# source_eagle.net
KiCad netlist of a schematic drawn in EAGLE
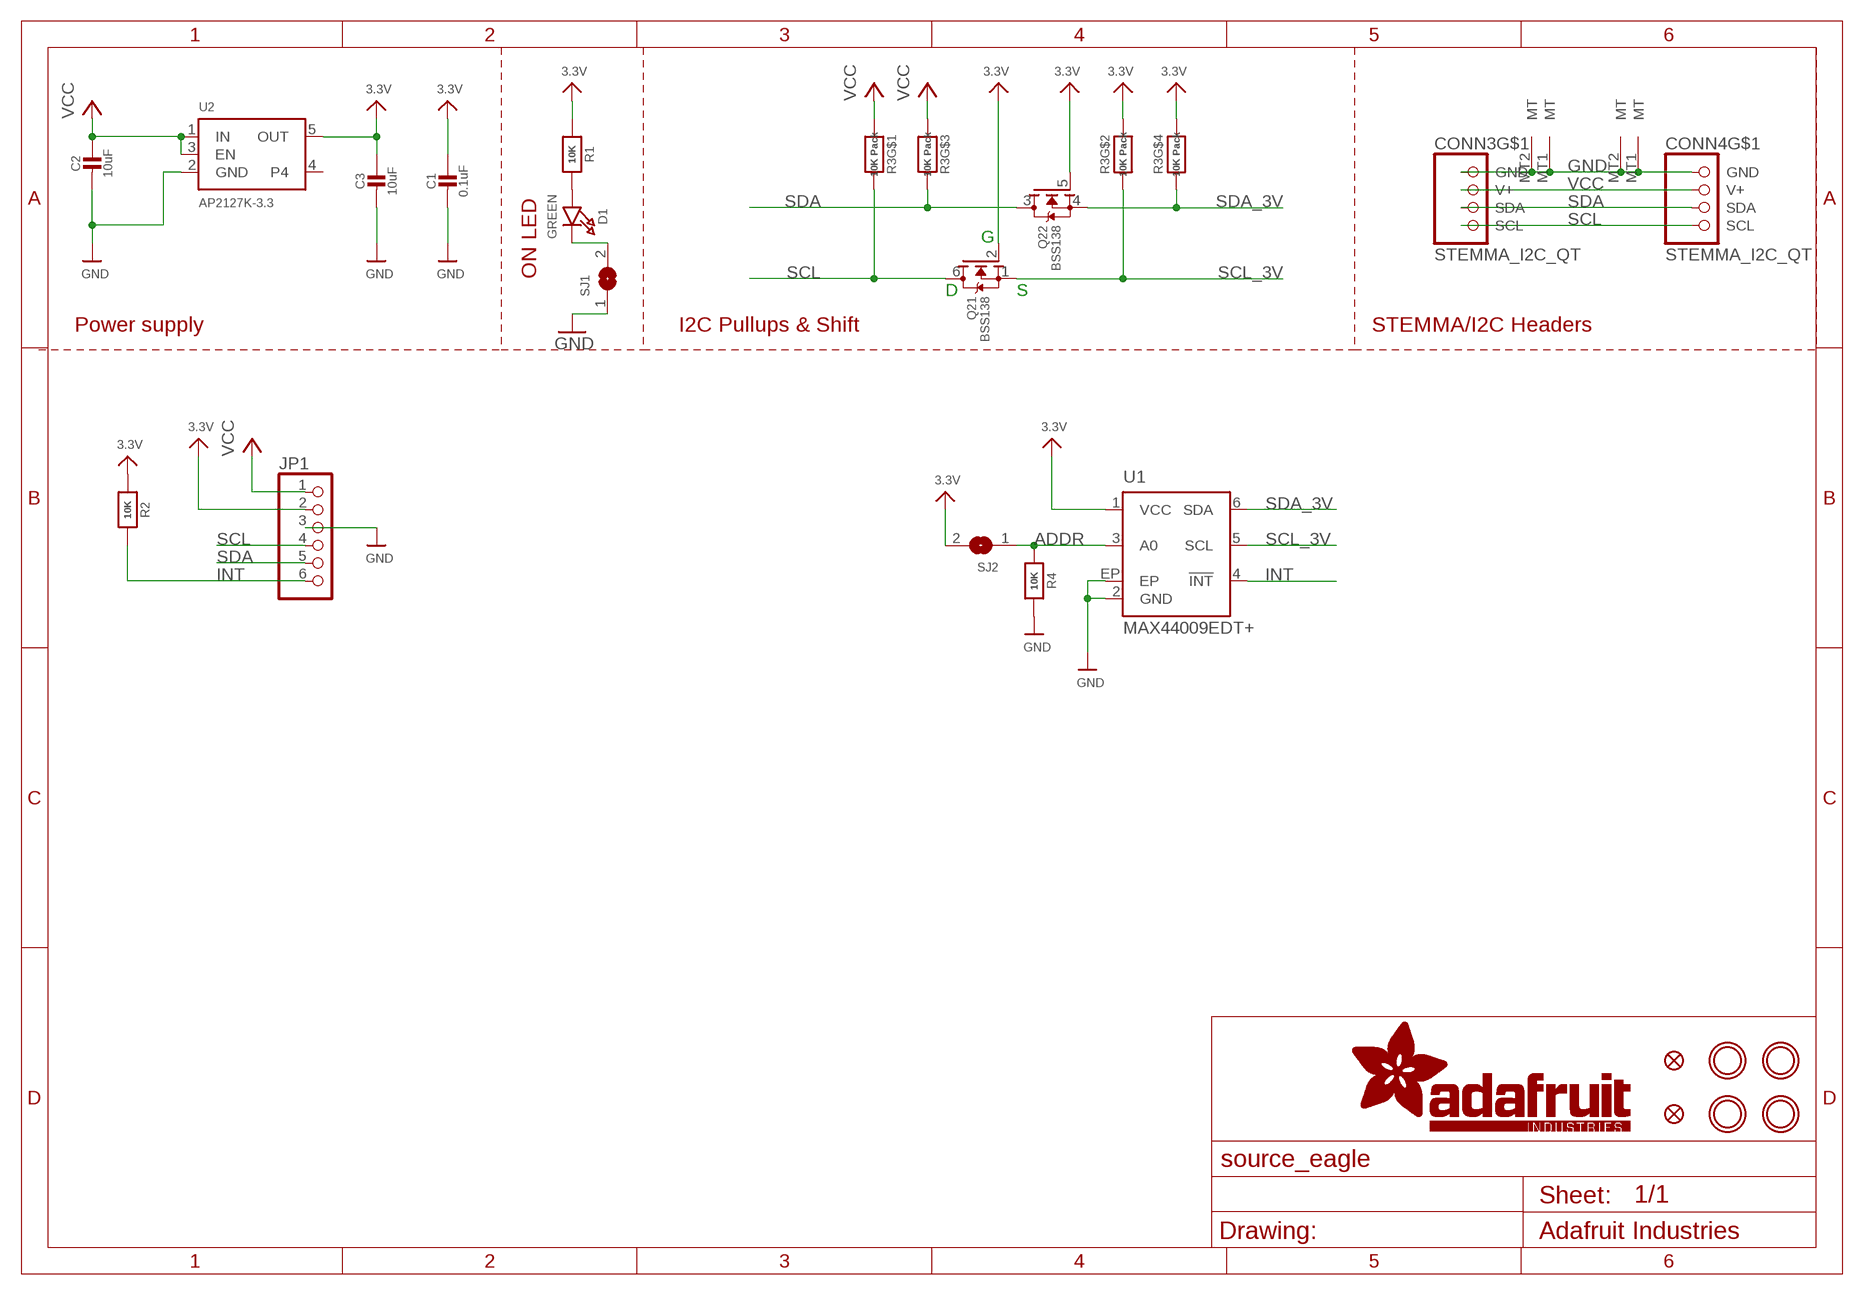
[diagram p0: schematic, sheet 1]

(export (version "E")
  (design (tool "Eeschema 10.0.6"))
  (components
    (comp (ref "C1")
      (value "0.1uF")
      (footprint "eagle-import:0603-NO")
      (libsource (lib "eagle-import") (part "CAP_CERAMIC0603_NO"))
    )
    (comp (ref "C2")
      (value "10uF")
      (footprint "eagle-import:0805-NO")
      (libsource (lib "eagle-import") (part "CAP_CERAMIC0805-NOOUTLINE"))
    )
    (comp (ref "C3")
      (value "10uF")
      (footprint "eagle-import:0805-NO")
      (libsource (lib "eagle-import") (part "CAP_CERAMIC0805-NOOUTLINE"))
    )
    (comp (ref "CONN3")
      (value "STEMMA_I2C_QT")
      (footprint "eagle-import:JST_SH4")
      (libsource (lib "eagle-import") (part "STEMMA_I2C_QT"))
    )
    (comp (ref "CONN4")
      (value "STEMMA_I2C_QT")
      (footprint "eagle-import:JST_SH4")
      (libsource (lib "eagle-import") (part "STEMMA_I2C_QT"))
    )
    (comp (ref "D1")
      (value "GREEN")
      (footprint "eagle-import:CHIPLED_0603_NOOUTLINE")
      (libsource (lib "eagle-import") (part "LED0603_NOOUTLINE"))
    )
    (comp (ref "FID3")
      (value "FIDUCIAL_0.5MM")
      (footprint "eagle-import:FIDUCIAL_0.5MM")
      (libsource (lib "eagle-import") (part "FIDUCIAL_0.5MM"))
    )
    (comp (ref "FID4")
      (value "FIDUCIAL_0.5MM")
      (footprint "eagle-import:FIDUCIAL_0.5MM")
      (libsource (lib "eagle-import") (part "FIDUCIAL_0.5MM"))
    )
    (comp (ref "JP1")
      (value "HEADER-1X670MIL")
      (footprint "eagle-import:1X06_ROUND_70")
      (libsource (lib "eagle-import") (part "HEADER-1X670MIL"))
    )
    (comp (ref "Q2")
      (value "BSS138")
      (footprint "eagle-import:SOT363")
      (libsource (lib "eagle-import") (part "MOSFET-N_DUAL"))
    )
    (comp (ref "R1")
      (value "10K")
      (footprint "eagle-import:0603-NO")
      (libsource (lib "eagle-import") (part "RESISTOR_0603_NOOUT"))
    )
    (comp (ref "R2")
      (value "10K")
      (footprint "eagle-import:0603-NO")
      (libsource (lib "eagle-import") (part "RESISTOR_0603_NOOUT"))
    )
    (comp (ref "R3")
      (value "10K Pack")
      (footprint "eagle-import:RESPACK_4X0603")
      (libsource (lib "eagle-import") (part "RESISTOR_4PACK"))
    )
    (comp (ref "R4")
      (value "10K")
      (footprint "eagle-import:0603-NO")
      (libsource (lib "eagle-import") (part "RESISTOR_0603_NOOUT"))
    )
    (comp (ref "SJ1")
      (value "SOLDERJUMPERCLOSED")
      (footprint "eagle-import:SOLDERJUMPER_CLOSEDWIRE")
      (libsource (lib "eagle-import") (part "SOLDERJUMPERCLOSED"))
    )
    (comp (ref "SJ2")
      (value "SOLDERJUMPER")
      (footprint "eagle-import:SOLDERJUMPER_ARROW_NOPASTE")
      (libsource (lib "eagle-import") (part "SOLDERJUMPER"))
    )
    (comp (ref "U$1")
      (value "MOUNTINGHOLE2.5")
      (footprint "eagle-import:MOUNTINGHOLE_2.5_PLATED")
      (libsource (lib "eagle-import") (part "MOUNTINGHOLE2.5"))
    )
    (comp (ref "U$17")
      (value "MOUNTINGHOLE2.5")
      (footprint "eagle-import:MOUNTINGHOLE_2.5_PLATED")
      (libsource (lib "eagle-import") (part "MOUNTINGHOLE2.5"))
    )
    (comp (ref "U$19")
      (value "MOUNTINGHOLE2.5")
      (footprint "eagle-import:MOUNTINGHOLE_2.5_PLATED")
      (libsource (lib "eagle-import") (part "MOUNTINGHOLE2.5"))
    )
    (comp (ref "U$21")
      (value "MOUNTINGHOLE2.5")
      (footprint "eagle-import:MOUNTINGHOLE_2.5_PLATED")
      (libsource (lib "eagle-import") (part "MOUNTINGHOLE2.5"))
    )
    (comp (ref "U1")
      (value "MAX44009EDT+")
      (footprint "eagle-import:UTDFN-OPTO-6")
      (libsource (lib "eagle-import") (part "MAX44009EDT+"))
    )
    (comp (ref "U2")
      (value "AP2127K-3.3")
      (footprint "eagle-import:SOT23-5")
      (libsource (lib "eagle-import") (part "VREG_SOT23-5"))
    )
  )
  (nets
    (net (code "1") (name "/ADDR") (class "Default")
      (node (ref "R4") (pin "1") (pinfunction "1_1") (pintype "passive"))
      (node (ref "SJ2") (pin "1") (pinfunction "1_1") (pintype "passive"))
      (node (ref "U1") (pin "3") (pinfunction "A0_3") (pintype "input"))
    )
    (net (code "2") (name "/INT") (class "Default")
      (node (ref "JP1") (pin "6") (pinfunction "6_6") (pintype "passive"))
      (node (ref "R2") (pin "2") (pinfunction "2_2") (pintype "passive"))
      (node (ref "U1") (pin "4") (pinfunction "~{INT}_4") (pintype "open_collector"))
    )
    (net (code "3") (name "/SCL") (class "Default")
      (node (ref "CONN3") (pin "4") (pinfunction "SCL_4") (pintype "passive"))
      (node (ref "CONN4") (pin "4") (pinfunction "SCL_4") (pintype "passive"))
      (node (ref "JP1") (pin "4") (pinfunction "4_4") (pintype "passive"))
      (node (ref "Q2") (pin "6") (pinfunction "D_6") (pintype "bidirectional"))
      (node (ref "R3") (pin "8") (pinfunction "2_8") (pintype "passive"))
    )
    (net (code "4") (name "/SCL_3V") (class "Default")
      (node (ref "Q2") (pin "1") (pinfunction "S_1") (pintype "bidirectional"))
      (node (ref "R3") (pin "7") (pinfunction "2_7") (pintype "passive"))
      (node (ref "U1") (pin "5") (pinfunction "SCL_5") (pintype "input"))
    )
    (net (code "5") (name "/SDA") (class "Default")
      (node (ref "CONN3") (pin "3") (pinfunction "SDA_3") (pintype "passive"))
      (node (ref "CONN4") (pin "3") (pinfunction "SDA_3") (pintype "passive"))
      (node (ref "JP1") (pin "5") (pinfunction "5_5") (pintype "passive"))
      (node (ref "Q2") (pin "3") (pinfunction "D_3") (pintype "bidirectional"))
      (node (ref "R3") (pin "6") (pinfunction "2_6") (pintype "passive"))
    )
    (net (code "6") (name "/SDA_3V") (class "Default")
      (node (ref "Q2") (pin "4") (pinfunction "S_4") (pintype "bidirectional"))
      (node (ref "R3") (pin "5") (pinfunction "2_5") (pintype "passive"))
      (node (ref "U1") (pin "6") (pinfunction "SDA_6") (pintype "bidirectional"))
    )
    (net (code "7") (name "3.3V") (class "Default")
      (node (ref "C1") (pin "1") (pinfunction "1_1") (pintype "passive"))
      (node (ref "C3") (pin "1") (pinfunction "1_1") (pintype "passive"))
      (node (ref "JP1") (pin "2") (pinfunction "2_2") (pintype "passive"))
      (node (ref "Q2") (pin "2") (pinfunction "G_2") (pintype "bidirectional"))
      (node (ref "Q2") (pin "5") (pinfunction "G_5") (pintype "bidirectional"))
      (node (ref "R1") (pin "1") (pinfunction "1_1") (pintype "passive"))
      (node (ref "R2") (pin "1") (pinfunction "1_1") (pintype "passive"))
      (node (ref "R3") (pin "2") (pinfunction "1_2") (pintype "passive"))
      (node (ref "R3") (pin "4") (pinfunction "1_4") (pintype "passive"))
      (node (ref "SJ2") (pin "2") (pinfunction "2_2") (pintype "passive"))
      (node (ref "U1") (pin "1") (pinfunction "VCC_1") (pintype "power_in"))
      (node (ref "U2") (pin "5") (pinfunction "OUT_5") (pintype "power_in"))
    )
    (net (code "8") (name "GND") (class "Default")
      (node (ref "C1") (pin "2") (pinfunction "2_2") (pintype "passive"))
      (node (ref "C2") (pin "2") (pinfunction "2_2") (pintype "passive"))
      (node (ref "C3") (pin "2") (pinfunction "2_2") (pintype "passive"))
      (node (ref "CONN3") (pin "1") (pinfunction "GND_1") (pintype "passive"))
      (node (ref "CONN3") (pin "MT1") (pinfunction "MT_MT1") (pintype "bidirectional"))
      (node (ref "CONN3") (pin "MT2") (pinfunction "MT_MT2") (pintype "bidirectional"))
      (node (ref "CONN4") (pin "1") (pinfunction "GND_1") (pintype "passive"))
      (node (ref "CONN4") (pin "MT1") (pinfunction "MT_MT1") (pintype "bidirectional"))
      (node (ref "CONN4") (pin "MT2") (pinfunction "MT_MT2") (pintype "bidirectional"))
      (node (ref "JP1") (pin "3") (pinfunction "3_3") (pintype "passive"))
      (node (ref "R4") (pin "2") (pinfunction "2_2") (pintype "passive"))
      (node (ref "SJ1") (pin "1") (pinfunction "1_1") (pintype "passive"))
      (node (ref "U1") (pin "2") (pinfunction "GND_2") (pintype "power_in"))
      (node (ref "U1") (pin "EP") (pinfunction "EP_EP") (pintype "power_in"))
      (node (ref "U2") (pin "2") (pinfunction "GND_2") (pintype "power_in"))
    )
    (net (code "9") (name "Net-(D1-PadA)") (class "Default")
      (node (ref "D1") (pin "A") (pinfunction "A_A") (pintype "passive"))
      (node (ref "R1") (pin "2") (pinfunction "2_2") (pintype "passive"))
    )
    (net (code "10") (name "Net-(D1-PadC)") (class "Default")
      (node (ref "D1") (pin "C") (pinfunction "C_C") (pintype "passive"))
      (node (ref "SJ1") (pin "2") (pinfunction "2_2") (pintype "passive"))
    )
    (net (code "11") (name "VCC") (class "Default")
      (node (ref "C2") (pin "1") (pinfunction "1_1") (pintype "passive"))
      (node (ref "CONN3") (pin "2") (pinfunction "V+_2") (pintype "passive"))
      (node (ref "CONN4") (pin "2") (pinfunction "V+_2") (pintype "passive"))
      (node (ref "JP1") (pin "1") (pinfunction "1_1") (pintype "passive"))
      (node (ref "R3") (pin "1") (pinfunction "1_1") (pintype "passive"))
      (node (ref "R3") (pin "3") (pinfunction "1_3") (pintype "passive"))
      (node (ref "U2") (pin "1") (pinfunction "IN_1") (pintype "power_in"))
      (node (ref "U2") (pin "3") (pinfunction "EN_3") (pintype "input"))
    )
    (net (code "12") (name "unconnected-(U2-P4-Pad4)") (class "Default")
      (node (ref "U2") (pin "4") (pinfunction "P4_4") (pintype "bidirectional"))
    )
  )
)
